# emc6907.net
KiCad netlist of a schematic drawn in EAGLE
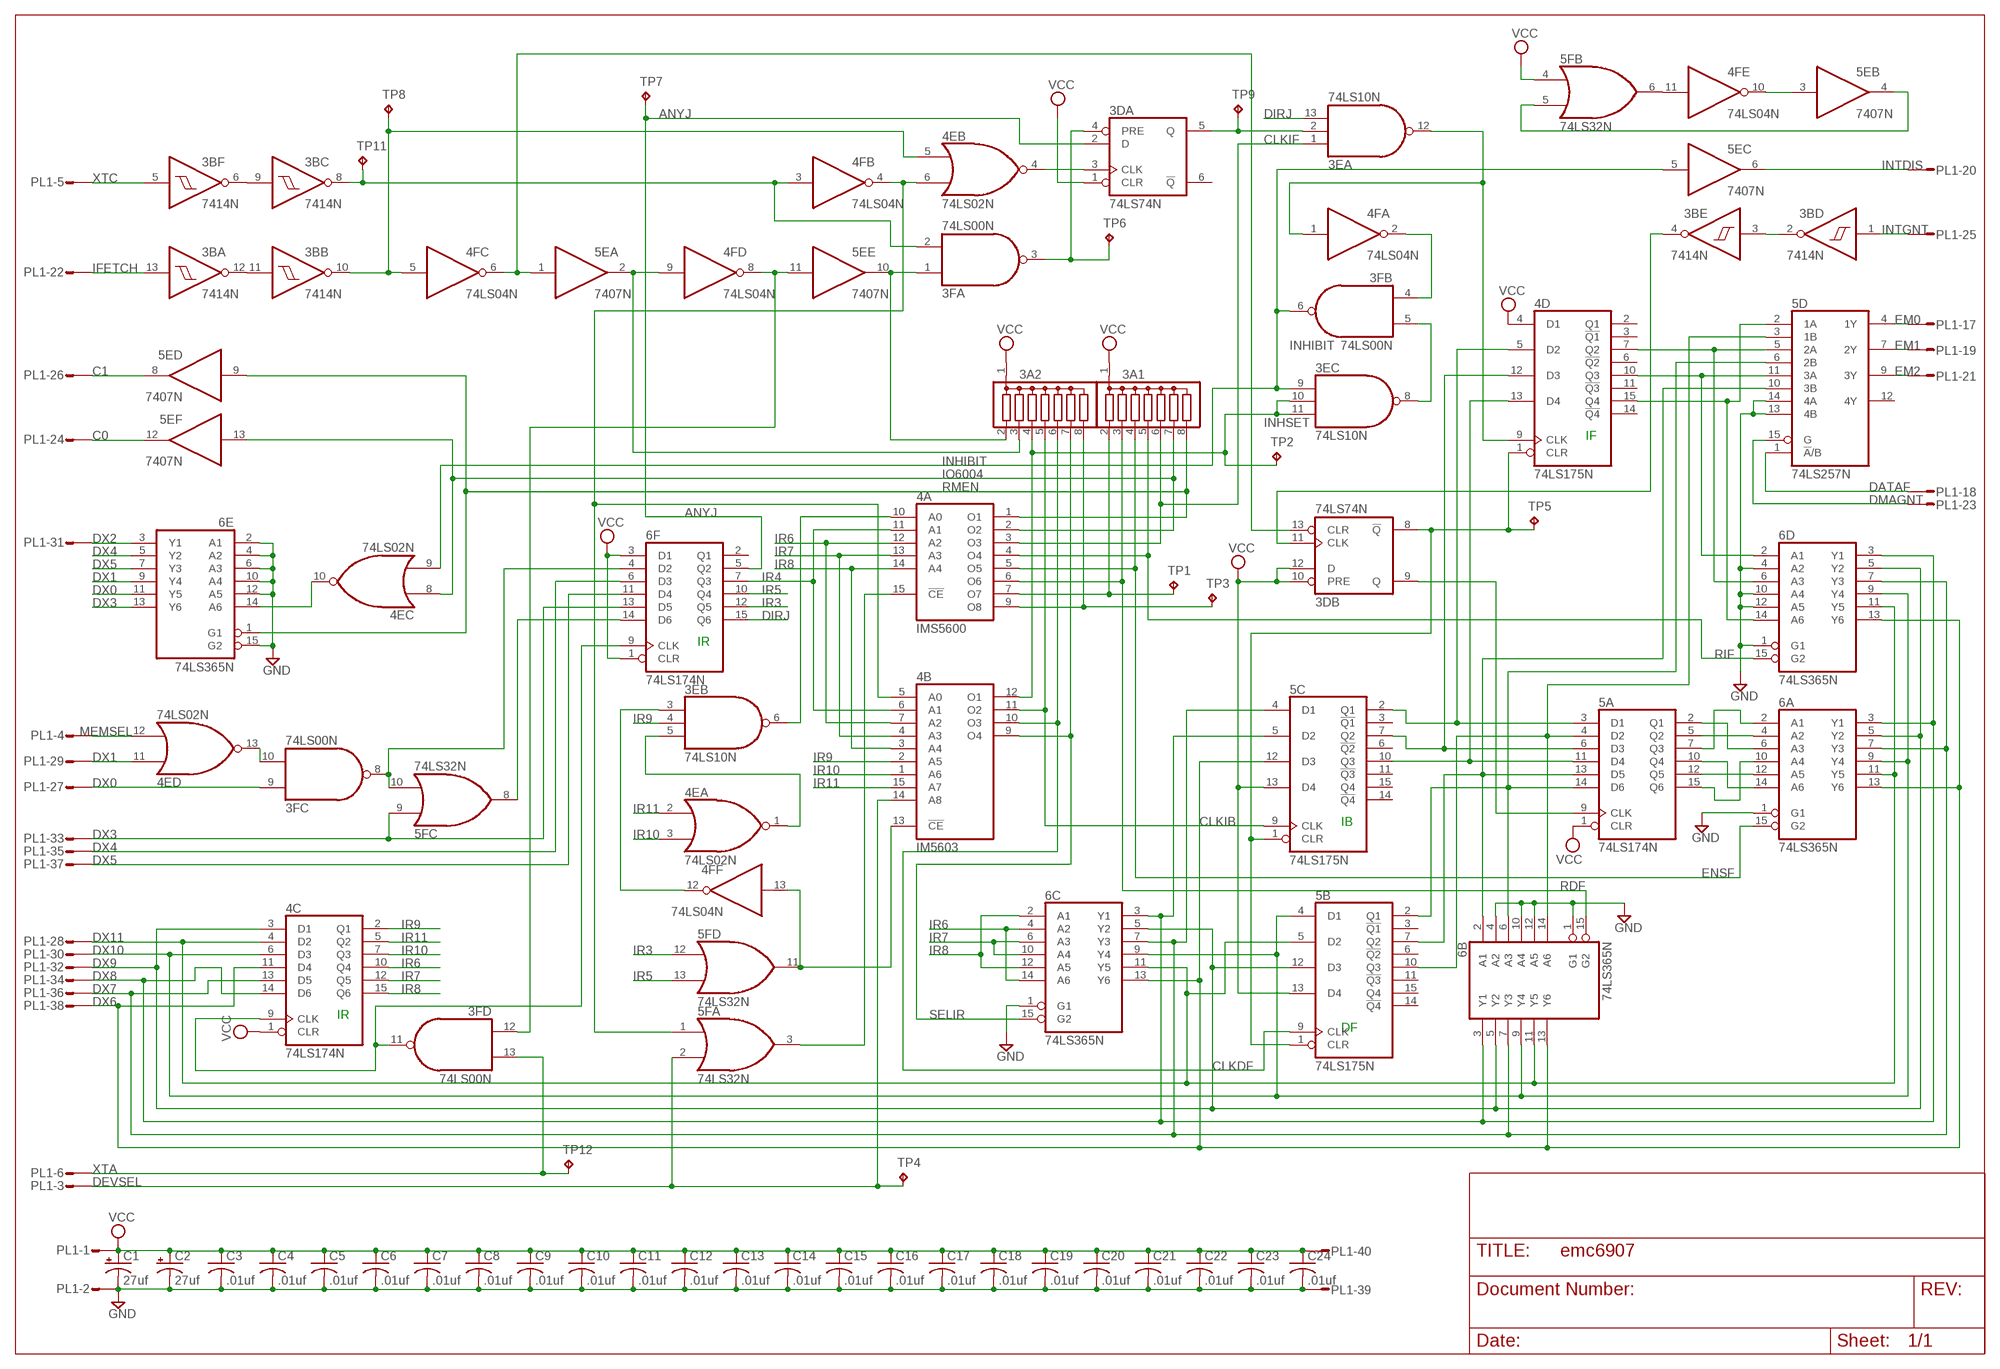
[diagram p0: schematic, sheet 1]

(export (version "E")
  (design (tool "Eeschema 10.0.6"))
  (components
    (comp (ref "3A1")
      (value "G07R")
      (footprint "eagle-import:SIL8")
      (libsource (lib "eagle-import") (part "G07R"))
    )
    (comp (ref "3A2")
      (value "G07R")
      (footprint "eagle-import:SIL8")
      (libsource (lib "eagle-import") (part "G07R"))
    )
    (comp (ref "3B")
      (value "7414N")
      (footprint "eagle-import:DIL14")
      (libsource (lib "eagle-import") (part "7414N"))
    )
    (comp (ref "3D")
      (value "74LS74N")
      (footprint "eagle-import:DIL14")
      (libsource (lib "eagle-import") (part "7474NLS"))
    )
    (comp (ref "3E")
      (value "74LS10N")
      (footprint "eagle-import:DIL14")
      (libsource (lib "eagle-import") (part "7410NLS"))
    )
    (comp (ref "3F")
      (value "74LS00N")
      (footprint "eagle-import:DIL14")
      (libsource (lib "eagle-import") (part "7400NLS"))
    )
    (comp (ref "4A")
      (value "IMS5600")
      (footprint "eagle-import:DIL16")
      (libsource (lib "eagle-import") (part "5600"))
    )
    (comp (ref "4B")
      (value "IM5603")
      (footprint "eagle-import:DIL16")
      (libsource (lib "eagle-import") (part "5306"))
    )
    (comp (ref "4C")
      (value "74LS174N")
      (footprint "eagle-import:DIL16")
      (libsource (lib "eagle-import") (part "74174NLS"))
    )
    (comp (ref "4D")
      (value "74LS175N")
      (footprint "eagle-import:DIL16")
      (libsource (lib "eagle-import") (part "74175NLS"))
    )
    (comp (ref "4E")
      (value "74LS02N")
      (footprint "eagle-import:DIL14")
      (libsource (lib "eagle-import") (part "7402NLS"))
    )
    (comp (ref "4F")
      (value "74LS04N")
      (footprint "eagle-import:DIL14")
      (libsource (lib "eagle-import") (part "7404NLS"))
    )
    (comp (ref "5A")
      (value "74LS174N")
      (footprint "eagle-import:DIL16")
      (libsource (lib "eagle-import") (part "74174NLS"))
    )
    (comp (ref "5B")
      (value "74LS175N")
      (footprint "eagle-import:DIL16")
      (libsource (lib "eagle-import") (part "74175NLS"))
    )
    (comp (ref "5C")
      (value "74LS175N")
      (footprint "eagle-import:DIL16")
      (libsource (lib "eagle-import") (part "74175NLS"))
    )
    (comp (ref "5D")
      (value "74LS257N")
      (footprint "eagle-import:DIL16")
      (libsource (lib "eagle-import") (part "74257NLS"))
    )
    (comp (ref "5E")
      (value "7407N")
      (footprint "eagle-import:DIL14")
      (libsource (lib "eagle-import") (part "7407N"))
    )
    (comp (ref "5F")
      (value "74LS32N")
      (footprint "eagle-import:DIL14")
      (libsource (lib "eagle-import") (part "7432NLS"))
    )
    (comp (ref "6A")
      (value "74LS365N")
      (footprint "eagle-import:DIL16")
      (libsource (lib "eagle-import") (part "74365NLS"))
    )
    (comp (ref "6B")
      (value "74LS365N")
      (footprint "eagle-import:DIL16")
      (libsource (lib "eagle-import") (part "74365NLS"))
    )
    (comp (ref "6C")
      (value "74LS365N")
      (footprint "eagle-import:DIL16")
      (libsource (lib "eagle-import") (part "74365NLS"))
    )
    (comp (ref "6D")
      (value "74LS365N")
      (footprint "eagle-import:DIL16")
      (libsource (lib "eagle-import") (part "74365NLS"))
    )
    (comp (ref "6E")
      (value "74LS365N")
      (footprint "eagle-import:DIL16")
      (libsource (lib "eagle-import") (part "74365NLS"))
    )
    (comp (ref "6F")
      (value "74LS174N")
      (footprint "eagle-import:DIL16")
      (libsource (lib "eagle-import") (part "74174NLS"))
    )
    (comp (ref "C1")
      (value "27uf")
      (footprint "eagle-import:E22-6")
      (libsource (lib "eagle-import") (part "CPOL-USE22-6AXIAL"))
    )
    (comp (ref "C2")
      (value "27uf")
      (footprint "eagle-import:E22-6")
      (libsource (lib "eagle-import") (part "CPOL-USE22-6AXIAL"))
    )
    (comp (ref "C3")
      (value ".01uf")
      (footprint "eagle-import:C050-025X075")
      (libsource (lib "eagle-import") (part "C-US050-025X075"))
    )
    (comp (ref "C4")
      (value ".01uf")
      (footprint "eagle-import:C050-025X075")
      (libsource (lib "eagle-import") (part "C-US050-025X075"))
    )
    (comp (ref "C5")
      (value ".01uf")
      (footprint "eagle-import:C050-025X075")
      (libsource (lib "eagle-import") (part "C-US050-025X075"))
    )
    (comp (ref "C6")
      (value ".01uf")
      (footprint "eagle-import:C050-025X075")
      (libsource (lib "eagle-import") (part "C-US050-025X075"))
    )
    (comp (ref "C7")
      (value ".01uf")
      (footprint "eagle-import:C050-025X075")
      (libsource (lib "eagle-import") (part "C-US050-025X075"))
    )
    (comp (ref "C8")
      (value ".01uf")
      (footprint "eagle-import:C050-025X075")
      (libsource (lib "eagle-import") (part "C-US050-025X075"))
    )
    (comp (ref "C9")
      (value ".01uf")
      (footprint "eagle-import:C050-025X075")
      (libsource (lib "eagle-import") (part "C-US050-025X075"))
    )
    (comp (ref "C10")
      (value ".01uf")
      (footprint "eagle-import:C050-025X075")
      (libsource (lib "eagle-import") (part "C-US050-025X075"))
    )
    (comp (ref "C11")
      (value ".01uf")
      (footprint "eagle-import:C050-025X075")
      (libsource (lib "eagle-import") (part "C-US050-025X075"))
    )
    (comp (ref "C12")
      (value ".01uf")
      (footprint "eagle-import:C050-025X075")
      (libsource (lib "eagle-import") (part "C-US050-025X075"))
    )
    (comp (ref "C13")
      (value ".01uf")
      (footprint "eagle-import:C050-025X075")
      (libsource (lib "eagle-import") (part "C-US050-025X075"))
    )
    (comp (ref "C14")
      (value ".01uf")
      (footprint "eagle-import:C050-025X075")
      (libsource (lib "eagle-import") (part "C-US050-025X075"))
    )
    (comp (ref "C15")
      (value ".01uf")
      (footprint "eagle-import:C050-025X075")
      (libsource (lib "eagle-import") (part "C-US050-025X075"))
    )
    (comp (ref "C16")
      (value ".01uf")
      (footprint "eagle-import:C050-025X075")
      (libsource (lib "eagle-import") (part "C-US050-025X075"))
    )
    (comp (ref "C17")
      (value ".01uf")
      (footprint "eagle-import:C050-025X075")
      (libsource (lib "eagle-import") (part "C-US050-025X075"))
    )
    (comp (ref "C18")
      (value ".01uf")
      (footprint "eagle-import:C050-025X075")
      (libsource (lib "eagle-import") (part "C-US050-025X075"))
    )
    (comp (ref "C19")
      (value ".01uf")
      (footprint "eagle-import:C050-025X075")
      (libsource (lib "eagle-import") (part "C-US050-025X075"))
    )
    (comp (ref "C20")
      (value ".01uf")
      (footprint "eagle-import:C050-025X075")
      (libsource (lib "eagle-import") (part "C-US050-025X075"))
    )
    (comp (ref "C21")
      (value ".01uf")
      (footprint "eagle-import:C050-025X075")
      (libsource (lib "eagle-import") (part "C-US050-025X075"))
    )
    (comp (ref "C22")
      (value ".01uf")
      (footprint "eagle-import:C050-025X075")
      (libsource (lib "eagle-import") (part "C-US050-025X075"))
    )
    (comp (ref "C23")
      (value ".01uf")
      (footprint "eagle-import:C050-025X075")
      (libsource (lib "eagle-import") (part "C-US050-025X075"))
    )
    (comp (ref "C24")
      (value ".01uf")
      (footprint "eagle-import:C050-025X075")
      (libsource (lib "eagle-import") (part "C-US050-025X075"))
    )
    (comp (ref "PL1")
      (value "40VS")
      (footprint "eagle-import:40V")
      (libsource (lib "eagle-import") (part "40VS"))
    )
    (comp (ref "TP1")
      (value "TPPAD1-13")
      (footprint "eagle-import:P1-13")
      (libsource (lib "eagle-import") (part "TPPAD1-13"))
    )
    (comp (ref "TP2")
      (value "TPPAD1-13")
      (footprint "eagle-import:P1-13")
      (libsource (lib "eagle-import") (part "TPPAD1-13"))
    )
    (comp (ref "TP3")
      (value "TPPAD1-13")
      (footprint "eagle-import:P1-13")
      (libsource (lib "eagle-import") (part "TPPAD1-13"))
    )
    (comp (ref "TP4")
      (value "TPPAD1-13")
      (footprint "eagle-import:P1-13")
      (libsource (lib "eagle-import") (part "TPPAD1-13"))
    )
    (comp (ref "TP5")
      (value "TPPAD1-13")
      (footprint "eagle-import:P1-13")
      (libsource (lib "eagle-import") (part "TPPAD1-13"))
    )
    (comp (ref "TP6")
      (value "TPPAD1-13")
      (footprint "eagle-import:P1-13")
      (libsource (lib "eagle-import") (part "TPPAD1-13"))
    )
    (comp (ref "TP7")
      (value "TPPAD1-13")
      (footprint "eagle-import:P1-13")
      (libsource (lib "eagle-import") (part "TPPAD1-13"))
    )
    (comp (ref "TP8")
      (value "TPPAD1-13")
      (footprint "eagle-import:P1-13")
      (libsource (lib "eagle-import") (part "TPPAD1-13"))
    )
    (comp (ref "TP9")
      (value "TPPAD1-13")
      (footprint "eagle-import:P1-13")
      (libsource (lib "eagle-import") (part "TPPAD1-13"))
    )
    (comp (ref "TP11")
      (value "TPPAD1-13")
      (footprint "eagle-import:P1-13")
      (libsource (lib "eagle-import") (part "TPPAD1-13"))
    )
    (comp (ref "TP12")
      (value "TPPAD1-13")
      (footprint "eagle-import:P1-13")
      (libsource (lib "eagle-import") (part "TPPAD1-13"))
    )
  )
  (nets
    (net (code "1") (name "/ANYJ") (class "Default")
      (node (ref "3D") (pin "2") (pinfunction "D_2") (pintype "input"))
      (node (ref "6F") (pin "5") (pinfunction "Q2_5") (pintype "output"))
      (node (ref "TP7") (pin "TP") (pinfunction "TP_TP") (pintype "input"))
    )
    (net (code "2") (name "/C0") (class "Default")
      (node (ref "5E") (pin "12") (pinfunction "O_12") (pintype "open_collector"))
      (node (ref "PL1") (pin "24") (pinfunction "S_24") (pintype "passive"))
    )
    (net (code "3") (name "/C1") (class "Default")
      (node (ref "5E") (pin "8") (pinfunction "O_8") (pintype "open_collector"))
      (node (ref "PL1") (pin "26") (pinfunction "S_26") (pintype "passive"))
    )
    (net (code "4") (name "/CLKDF") (class "Default")
      (node (ref "3A2") (pin "6") (pinfunction "6_6") (pintype "passive"))
      (node (ref "4B") (pin "10") (pinfunction "O3_10") (pintype "tri_state"))
      (node (ref "5B") (pin "9") (pinfunction "CLK_9") (pintype "input"))
    )
    (net (code "5") (name "/CLKIB") (class "Default")
      (node (ref "3A2") (pin "5") (pinfunction "5_5") (pintype "passive"))
      (node (ref "4B") (pin "11") (pinfunction "O2_11") (pintype "tri_state"))
      (node (ref "5C") (pin "9") (pinfunction "CLK_9") (pintype "input"))
    )
    (net (code "6") (name "/CLKIF") (class "Default")
      (node (ref "3A1") (pin "6") (pinfunction "6_6") (pintype "passive"))
      (node (ref "3E") (pin "1") (pinfunction "I0_1") (pintype "input"))
      (node (ref "4A") (pin "3") (pinfunction "O3_3") (pintype "open_collector"))
    )
    (net (code "7") (name "/DATAF") (class "Default")
      (node (ref "5D") (pin "1") (pinfunction "~{A}/B_1") (pintype "input"))
      (node (ref "PL1") (pin "18") (pinfunction "S_18") (pintype "passive"))
    )
    (net (code "8") (name "/DEVSEL") (class "Default")
      (node (ref "4B") (pin "14") (pinfunction "A8_14") (pintype "input"))
      (node (ref "5F") (pin "2") (pinfunction "I1_2") (pintype "input"))
      (node (ref "PL1") (pin "3") (pinfunction "S_3") (pintype "passive"))
      (node (ref "TP4") (pin "TP") (pinfunction "TP_TP") (pintype "input"))
    )
    (net (code "9") (name "/DIRJ") (class "Default")
      (node (ref "3E") (pin "13") (pinfunction "I2_13") (pintype "input"))
      (node (ref "6F") (pin "15") (pinfunction "Q6_15") (pintype "output"))
    )
    (net (code "10") (name "/DMAGNT") (class "Default")
      (node (ref "5D") (pin "15") (pinfunction "G_15") (pintype "input"))
      (node (ref "PL1") (pin "23") (pinfunction "S_23") (pintype "passive"))
    )
    (net (code "11") (name "/DX0") (class "Default")
      (node (ref "3F") (pin "9") (pinfunction "I0_9") (pintype "input"))
      (node (ref "6E") (pin "11") (pinfunction "Y5_11") (pintype "tri_state"))
      (node (ref "PL1") (pin "27") (pinfunction "S_27") (pintype "passive"))
    )
    (net (code "12") (name "/DX1") (class "Default")
      (node (ref "4E") (pin "11") (pinfunction "I0_11") (pintype "input"))
      (node (ref "6E") (pin "9") (pinfunction "Y4_9") (pintype "tri_state"))
      (node (ref "PL1") (pin "29") (pinfunction "S_29") (pintype "passive"))
    )
    (net (code "13") (name "/DX2") (class "Default")
      (node (ref "6E") (pin "3") (pinfunction "Y1_3") (pintype "tri_state"))
      (node (ref "PL1") (pin "31") (pinfunction "S_31") (pintype "passive"))
    )
    (net (code "14") (name "/DX3") (class "Default")
      (node (ref "5F") (pin "9") (pinfunction "I0_9") (pintype "input"))
      (node (ref "6E") (pin "13") (pinfunction "Y6_13") (pintype "tri_state"))
      (node (ref "6F") (pin "13") (pinfunction "D5_13") (pintype "input"))
      (node (ref "PL1") (pin "33") (pinfunction "S_33") (pintype "passive"))
    )
    (net (code "15") (name "/DX4") (class "Default")
      (node (ref "6E") (pin "5") (pinfunction "Y2_5") (pintype "tri_state"))
      (node (ref "6F") (pin "6") (pinfunction "D3_6") (pintype "input"))
      (node (ref "PL1") (pin "35") (pinfunction "S_35") (pintype "passive"))
    )
    (net (code "16") (name "/DX5") (class "Default")
      (node (ref "6E") (pin "7") (pinfunction "Y3_7") (pintype "tri_state"))
      (node (ref "6F") (pin "11") (pinfunction "D4_11") (pintype "input"))
      (node (ref "PL1") (pin "37") (pinfunction "S_37") (pintype "passive"))
    )
    (net (code "17") (name "/DX6") (class "Default")
      (node (ref "4C") (pin "11") (pinfunction "D4_11") (pintype "input"))
      (node (ref "5C") (pin "12") (pinfunction "D3_12") (pintype "input"))
      (node (ref "6A") (pin "13") (pinfunction "Y6_13") (pintype "tri_state"))
      (node (ref "6B") (pin "13") (pinfunction "Y6_13") (pintype "tri_state"))
      (node (ref "6C") (pin "13") (pinfunction "Y6_13") (pintype "tri_state"))
      (node (ref "6D") (pin "13") (pinfunction "Y6_13") (pintype "tri_state"))
      (node (ref "PL1") (pin "38") (pinfunction "S_38") (pintype "passive"))
    )
    (net (code "18") (name "/DX7") (class "Default")
      (node (ref "4C") (pin "13") (pinfunction "D5_13") (pintype "input"))
      (node (ref "5C") (pin "4") (pinfunction "D1_4") (pintype "input"))
      (node (ref "6A") (pin "7") (pinfunction "Y3_7") (pintype "tri_state"))
      (node (ref "6B") (pin "7") (pinfunction "Y3_7") (pintype "tri_state"))
      (node (ref "6C") (pin "7") (pinfunction "Y3_7") (pintype "tri_state"))
      (node (ref "6D") (pin "7") (pinfunction "Y3_7") (pintype "tri_state"))
      (node (ref "PL1") (pin "36") (pinfunction "S_36") (pintype "passive"))
    )
    (net (code "19") (name "/DX8") (class "Default")
      (node (ref "4C") (pin "14") (pinfunction "D6_14") (pintype "input"))
      (node (ref "5C") (pin "5") (pinfunction "D2_5") (pintype "input"))
      (node (ref "6A") (pin "3") (pinfunction "Y1_3") (pintype "tri_state"))
      (node (ref "6B") (pin "3") (pinfunction "Y1_3") (pintype "tri_state"))
      (node (ref "6C") (pin "3") (pinfunction "Y1_3") (pintype "tri_state"))
      (node (ref "6D") (pin "3") (pinfunction "Y1_3") (pintype "tri_state"))
      (node (ref "PL1") (pin "34") (pinfunction "S_34") (pintype "passive"))
    )
    (net (code "20") (name "/DX9") (class "Default")
      (node (ref "4C") (pin "3") (pinfunction "D1_3") (pintype "input"))
      (node (ref "5B") (pin "12") (pinfunction "D3_12") (pintype "input"))
      (node (ref "6A") (pin "5") (pinfunction "Y2_5") (pintype "tri_state"))
      (node (ref "6B") (pin "5") (pinfunction "Y2_5") (pintype "tri_state"))
      (node (ref "6C") (pin "5") (pinfunction "Y2_5") (pintype "tri_state"))
      (node (ref "6D") (pin "5") (pinfunction "Y2_5") (pintype "tri_state"))
      (node (ref "PL1") (pin "32") (pinfunction "S_32") (pintype "passive"))
    )
    (net (code "21") (name "/DX10") (class "Default")
      (node (ref "4C") (pin "6") (pinfunction "D3_6") (pintype "input"))
      (node (ref "5B") (pin "4") (pinfunction "D1_4") (pintype "input"))
      (node (ref "6A") (pin "9") (pinfunction "Y4_9") (pintype "tri_state"))
      (node (ref "6B") (pin "9") (pinfunction "Y4_9") (pintype "tri_state"))
      (node (ref "6C") (pin "9") (pinfunction "Y4_9") (pintype "tri_state"))
      (node (ref "6D") (pin "9") (pinfunction "Y4_9") (pintype "tri_state"))
      (node (ref "PL1") (pin "30") (pinfunction "S_30") (pintype "passive"))
    )
    (net (code "22") (name "/DX11") (class "Default")
      (node (ref "4C") (pin "4") (pinfunction "D2_4") (pintype "input"))
      (node (ref "5B") (pin "5") (pinfunction "D2_5") (pintype "input"))
      (node (ref "6A") (pin "11") (pinfunction "Y5_11") (pintype "tri_state"))
      (node (ref "6B") (pin "11") (pinfunction "Y5_11") (pintype "tri_state"))
      (node (ref "6C") (pin "11") (pinfunction "Y5_11") (pintype "tri_state"))
      (node (ref "6D") (pin "11") (pinfunction "Y5_11") (pintype "tri_state"))
      (node (ref "PL1") (pin "28") (pinfunction "S_28") (pintype "passive"))
    )
    (net (code "23") (name "/EM0") (class "Default")
      (node (ref "5D") (pin "4") (pinfunction "1Y_4") (pintype "tri_state"))
      (node (ref "PL1") (pin "17") (pinfunction "S_17") (pintype "passive"))
    )
    (net (code "24") (name "/EM1") (class "Default")
      (node (ref "5D") (pin "7") (pinfunction "2Y_7") (pintype "tri_state"))
      (node (ref "PL1") (pin "19") (pinfunction "S_19") (pintype "passive"))
    )
    (net (code "25") (name "/EM2") (class "Default")
      (node (ref "5D") (pin "9") (pinfunction "3Y_9") (pintype "tri_state"))
      (node (ref "PL1") (pin "21") (pinfunction "S_21") (pintype "passive"))
    )
    (net (code "26") (name "/ENSF") (class "Default")
      (node (ref "3A1") (pin "4") (pinfunction "4_4") (pintype "passive"))
      (node (ref "4A") (pin "5") (pinfunction "O5_5") (pintype "open_collector"))
      (node (ref "6A") (pin "15") (pinfunction "G2_15") (pintype "input"))
    )
    (net (code "27") (name "/IFETCH") (class "Default")
      (node (ref "3B") (pin "13") (pinfunction "I_13") (pintype "input"))
      (node (ref "PL1") (pin "22") (pinfunction "S_22") (pintype "passive"))
    )
    (net (code "28") (name "/INHIBIT") (class "Default")
      (node (ref "3E") (pin "9") (pinfunction "I0_9") (pintype "input"))
      (node (ref "3F") (pin "6") (pinfunction "O_6") (pintype "output"))
      (node (ref "4E") (pin "9") (pinfunction "I1_9") (pintype "input"))
      (node (ref "5E") (pin "5") (pinfunction "I_5") (pintype "input"))
    )
    (net (code "29") (name "/INHSET") (class "Default")
      (node (ref "3A2") (pin "4") (pinfunction "4_4") (pintype "passive"))
      (node (ref "3E") (pin "10") (pinfunction "I1_10") (pintype "input"))
      (node (ref "3E") (pin "11") (pinfunction "I2_11") (pintype "input"))
      (node (ref "4B") (pin "12") (pinfunction "O1_12") (pintype "tri_state"))
      (node (ref "TP2") (pin "TP") (pinfunction "TP_TP") (pintype "input"))
    )
    (net (code "30") (name "/INTDIS") (class "Default")
      (node (ref "5E") (pin "6") (pinfunction "O_6") (pintype "open_collector"))
      (node (ref "PL1") (pin "20") (pinfunction "S_20") (pintype "passive"))
    )
    (net (code "31") (name "/INTGNT") (class "Default")
      (node (ref "3B") (pin "1") (pinfunction "I_1") (pintype "input"))
      (node (ref "PL1") (pin "25") (pinfunction "S_25") (pintype "passive"))
    )
    (net (code "32") (name "/IO6004") (class "Default")
      (node (ref "3A1") (pin "7") (pinfunction "7_7") (pintype "passive"))
      (node (ref "4A") (pin "2") (pinfunction "O2_2") (pintype "open_collector"))
      (node (ref "4E") (pin "8") (pinfunction "I0_8") (pintype "input"))
      (node (ref "5E") (pin "13") (pinfunction "I_13") (pintype "input"))
    )
    (net (code "33") (name "/IR3") (class "Default")
      (node (ref "5F") (pin "12") (pinfunction "I0_12") (pintype "input"))
      (node (ref "6F") (pin "12") (pinfunction "Q5_12") (pintype "output"))
    )
    (net (code "34") (name "/IR4") (class "Default")
      (node (ref "4A") (pin "11") (pinfunction "A1_11") (pintype "input"))
      (node (ref "4B") (pin "6") (pinfunction "A1_6") (pintype "input"))
      (node (ref "6F") (pin "7") (pinfunction "Q3_7") (pintype "output"))
    )
    (net (code "35") (name "/IR5") (class "Default")
      (node (ref "5F") (pin "13") (pinfunction "I1_13") (pintype "input"))
      (node (ref "6F") (pin "10") (pinfunction "Q4_10") (pintype "output"))
    )
    (net (code "36") (name "/IR6") (class "Default")
      (node (ref "4A") (pin "12") (pinfunction "A2_12") (pintype "input"))
      (node (ref "4B") (pin "7") (pinfunction "A2_7") (pintype "input"))
      (node (ref "4C") (pin "10") (pinfunction "Q4_10") (pintype "output"))
      (node (ref "6C") (pin "14") (pinfunction "A6_14") (pintype "input"))
      (node (ref "6C") (pin "4") (pinfunction "A2_4") (pintype "input"))
    )
    (net (code "37") (name "/IR7") (class "Default")
      (node (ref "4A") (pin "13") (pinfunction "A3_13") (pintype "input"))
      (node (ref "4B") (pin "4") (pinfunction "A3_4") (pintype "input"))
      (node (ref "4C") (pin "12") (pinfunction "Q5_12") (pintype "output"))
      (node (ref "6C") (pin "10") (pinfunction "A4_10") (pintype "input"))
      (node (ref "6C") (pin "6") (pinfunction "A3_6") (pintype "input"))
    )
    (net (code "38") (name "/IR8") (class "Default")
      (node (ref "4A") (pin "14") (pinfunction "A4_14") (pintype "input"))
      (node (ref "4B") (pin "3") (pinfunction "A4_3") (pintype "input"))
      (node (ref "4C") (pin "15") (pinfunction "Q6_15") (pintype "output"))
      (node (ref "6C") (pin "12") (pinfunction "A5_12") (pintype "input"))
      (node (ref "6C") (pin "2") (pinfunction "A1_2") (pintype "input"))
    )
    (net (code "39") (name "/IR9") (class "Default")
      (node (ref "3E") (pin "4") (pinfunction "I1_4") (pintype "input"))
      (node (ref "4B") (pin "2") (pinfunction "A5_2") (pintype "input"))
      (node (ref "4C") (pin "2") (pinfunction "Q1_2") (pintype "output"))
    )
    (net (code "40") (name "/IR10") (class "Default")
      (node (ref "4B") (pin "1") (pinfunction "A6_1") (pintype "input"))
      (node (ref "4C") (pin "7") (pinfunction "Q3_7") (pintype "output"))
      (node (ref "4E") (pin "3") (pinfunction "I1_3") (pintype "input"))
    )
    (net (code "41") (name "/IR11") (class "Default")
      (node (ref "4B") (pin "15") (pinfunction "A7_15") (pintype "input"))
      (node (ref "4C") (pin "5") (pinfunction "Q2_5") (pintype "output"))
      (node (ref "4E") (pin "2") (pinfunction "I0_2") (pintype "input"))
    )
    (net (code "42") (name "/MEMSEL") (class "Default")
      (node (ref "4E") (pin "12") (pinfunction "I1_12") (pintype "input"))
      (node (ref "PL1") (pin "4") (pinfunction "S_4") (pintype "passive"))
    )
    (net (code "43") (name "/RDF") (class "Default")
      (node (ref "3A1") (pin "3") (pinfunction "3_3") (pintype "passive"))
      (node (ref "4A") (pin "6") (pinfunction "O6_6") (pintype "open_collector"))
      (node (ref "6B") (pin "15") (pinfunction "G2_15") (pintype "input"))
    )
    (net (code "44") (name "/RIF") (class "Default")
      (node (ref "3A1") (pin "5") (pinfunction "5_5") (pintype "passive"))
      (node (ref "4A") (pin "4") (pinfunction "O4_4") (pintype "open_collector"))
      (node (ref "6D") (pin "15") (pinfunction "G2_15") (pintype "input"))
    )
    (net (code "45") (name "/RMEN") (class "Default")
      (node (ref "3A1") (pin "8") (pinfunction "8_8") (pintype "passive"))
      (node (ref "4A") (pin "1") (pinfunction "O1_1") (pintype "open_collector"))
      (node (ref "5E") (pin "9") (pinfunction "I_9") (pintype "input"))
      (node (ref "6E") (pin "1") (pinfunction "G1_1") (pintype "input"))
    )
    (net (code "46") (name "/SELIR") (class "Default")
      (node (ref "3A2") (pin "7") (pinfunction "7_7") (pintype "passive"))
      (node (ref "4B") (pin "9") (pinfunction "O4_9") (pintype "tri_state"))
      (node (ref "6C") (pin "15") (pinfunction "G2_15") (pintype "input"))
    )
    (net (code "47") (name "/XTA") (class "Default")
      (node (ref "3F") (pin "13") (pinfunction "I1_13") (pintype "input"))
      (node (ref "PL1") (pin "6") (pinfunction "S_6") (pintype "passive"))
      (node (ref "TP12") (pin "TP") (pinfunction "TP_TP") (pintype "input"))
    )
    (net (code "48") (name "/XTC") (class "Default")
      (node (ref "3B") (pin "5") (pinfunction "I_5") (pintype "input"))
      (node (ref "PL1") (pin "5") (pinfunction "S_5") (pintype "passive"))
    )
    (net (code "49") (name "GND") (class "Default")
      (node (ref "5D") (pin "13") (pinfunction "4B_13") (pintype "input"))
      (node (ref "5D") (pin "14") (pinfunction "4A_14") (pintype "input"))
      (node (ref "6A") (pin "1") (pinfunction "G1_1") (pintype "input"))
      (node (ref "6B") (pin "1") (pinfunction "G1_1") (pintype "input"))
      (node (ref "6B") (pin "10") (pinfunction "A4_10") (pintype "input"))
      (node (ref "6B") (pin "12") (pinfunction "A5_12") (pintype "input"))
      (node (ref "6B") (pin "4") (pinfunction "A2_4") (pintype "input"))
      (node (ref "6C") (pin "1") (pinfunction "G1_1") (pintype "input"))
      (node (ref "6D") (pin "1") (pinfunction "G1_1") (pintype "input"))
      (node (ref "6D") (pin "10") (pinfunction "A4_10") (pintype "input"))
      (node (ref "6D") (pin "12") (pinfunction "A5_12") (pintype "input"))
      (node (ref "6D") (pin "4") (pinfunction "A2_4") (pintype "input"))
      (node (ref "6E") (pin "10") (pinfunction "A4_10") (pintype "input"))
      (node (ref "6E") (pin "12") (pinfunction "A5_12") (pintype "input"))
      (node (ref "6E") (pin "15") (pinfunction "G2_15") (pintype "input"))
      (node (ref "6E") (pin "2") (pinfunction "A1_2") (pintype "input"))
      (node (ref "6E") (pin "4") (pinfunction "A2_4") (pintype "input"))
      (node (ref "6E") (pin "6") (pinfunction "A3_6") (pintype "input"))
      (node (ref "C1") (pin "-") (pinfunction "-_-") (pintype "passive"))
      (node (ref "C10") (pin "2") (pinfunction "2_2") (pintype "passive"))
      (node (ref "C11") (pin "2") (pinfunction "2_2") (pintype "passive"))
      (node (ref "C12") (pin "2") (pinfunction "2_2") (pintype "passive"))
      (node (ref "C13") (pin "2") (pinfunction "2_2") (pintype "passive"))
      (node (ref "C14") (pin "2") (pinfunction "2_2") (pintype "passive"))
      (node (ref "C15") (pin "2") (pinfunction "2_2") (pintype "passive"))
      (node (ref "C16") (pin "2") (pinfunction "2_2") (pintype "passive"))
      (node (ref "C17") (pin "2") (pinfunction "2_2") (pintype "passive"))
      (node (ref "C18") (pin "2") (pinfunction "2_2") (pintype "passive"))
      (node (ref "C19") (pin "2") (pinfunction "2_2") (pintype "passive"))
      (node (ref "C2") (pin "-") (pinfunction "-_-") (pintype "passive"))
      (node (ref "C20") (pin "2") (pinfunction "2_2") (pintype "passive"))
      (node (ref "C21") (pin "2") (pinfunction "2_2") (pintype "passive"))
      (node (ref "C22") (pin "2") (pinfunction "2_2") (pintype "passive"))
      (node (ref "C23") (pin "2") (pinfunction "2_2") (pintype "passive"))
      (node (ref "C24") (pin "2") (pinfunction "2_2") (pintype "passive"))
      (node (ref "C3") (pin "2") (pinfunction "2_2") (pintype "passive"))
      (node (ref "C4") (pin "2") (pinfunction "2_2") (pintype "passive"))
      (node (ref "C5") (pin "2") (pinfunction "2_2") (pintype "passive"))
      (node (ref "C6") (pin "2") (pinfunction "2_2") (pintype "passive"))
      (node (ref "C7") (pin "2") (pinfunction "2_2") (pintype "passive"))
      (node (ref "C8") (pin "2") (pinfunction "2_2") (pintype "passive"))
      (node (ref "C9") (pin "2") (pinfunction "2_2") (pintype "passive"))
      (node (ref "PL1") (pin "2") (pinfunction "S_2") (pintype "passive"))
      (node (ref "PL1") (pin "39") (pinfunction "S_39") (pintype "passive"))
    )
    (net (code "50") (name "Net-(3BA-O)") (class "Default")
      (node (ref "3B") (pin "11") (pinfunction "I_11") (pintype "input"))
      (node (ref "3B") (pin "12") (pinfunction "O_12") (pintype "output"))
    )
    (net (code "51") (name "Net-(3BB-O)") (class "Default")
      (node (ref "3B") (pin "10") (pinfunction "O_10") (pintype "output"))
      (node (ref "4E") (pin "5") (pinfunction "I0_5") (pintype "input"))
      (node (ref "4F") (pin "5") (pinfunction "I_5") (pintype "input"))
      (node (ref "TP8") (pin "TP") (pinfunction "TP_TP") (pintype "input"))
    )
    (net (code "52") (name "Net-(3BC-I)") (class "Default")
      (node (ref "3B") (pin "6") (pinfunction "O_6") (pintype "output"))
      (node (ref "3B") (pin "9") (pinfunction "I_9") (pintype "input"))
    )
    (net (code "53") (name "Net-(3BC-O)") (class "Default")
      (node (ref "3B") (pin "8") (pinfunction "O_8") (pintype "output"))
      (node (ref "3F") (pin "2") (pinfunction "I1_2") (pintype "input"))
      (node (ref "4F") (pin "3") (pinfunction "I_3") (pintype "input"))
      (node (ref "TP11") (pin "TP") (pinfunction "TP_TP") (pintype "input"))
    )
    (net (code "54") (name "Net-(3BD-O)") (class "Default")
      (node (ref "3B") (pin "2") (pinfunction "O_2") (pintype "output"))
      (node (ref "3B") (pin "3") (pinfunction "I_3") (pintype "input"))
    )
    (net (code "55") (name "Net-(3BE-O)") (class "Default")
      (node (ref "3B") (pin "4") (pinfunction "O_4") (pintype "output"))
      (node (ref "3D") (pin "11") (pinfunction "CLK_11") (pintype "input"))
    )
    (net (code "56") (name "Net-(3DA-CLK)") (class "Default")
      (node (ref "3D") (pin "3") (pinfunction "CLK_3") (pintype "input"))
      (node (ref "4E") (pin "4") (pinfunction "O_4") (pintype "output"))
    )
    (net (code "57") (name "Net-(3DA-PRE)") (class "Default")
      (node (ref "3D") (pin "4") (pinfunction "PRE_4") (pintype "input"))
      (node (ref "3F") (pin "3") (pinfunction "O_3") (pintype "output"))
      (node (ref "TP6") (pin "TP") (pinfunction "TP_TP") (pintype "input"))
    )
    (net (code "58") (name "Net-(3DA-Q)") (class "Default")
      (node (ref "3D") (pin "5") (pinfunction "Q_5") (pintype "output"))
      (node (ref "3E") (pin "2") (pinfunction "I1_2") (pintype "input"))
      (node (ref "TP9") (pin "TP") (pinfunction "TP_TP") (pintype "input"))
    )
    (net (code "59") (name "Net-(3DB-CLR)") (class "Default")
      (node (ref "3D") (pin "13") (pinfunction "CLR_13") (pintype "input"))
      (node (ref "4F") (pin "6") (pinfunction "O_6") (pintype "output"))
      (node (ref "5E") (pin "1") (pinfunction "I_1") (pintype "input"))
    )
    (net (code "60") (name "Net-(3DB-Q)") (class "Default")
      (node (ref "3D") (pin "9") (pinfunction "Q_9") (pintype "output"))
      (node (ref "5A") (pin "9") (pinfunction "CLK_9") (pintype "input"))
    )
    (net (code "61") (name "Net-(3DB-~{Q})") (class "Default")
      (node (ref "3D") (pin "8") (pinfunction "~{Q}_8") (pintype "output"))
      (node (ref "4D") (pin "1") (pinfunction "CLR_1") (pintype "input"))
      (node (ref "5B") (pin "1") (pinfunction "CLR_1") (pintype "input"))
      (node (ref "5C") (pin "1") (pinfunction "CLR_1") (pintype "input"))
      (node (ref "TP5") (pin "TP") (pinfunction "TP_TP") (pintype "input"))
    )
    (net (code "62") (name "Net-(3EA-O)") (class "Default")
      (node (ref "3E") (pin "12") (pinfunction "O_12") (pintype "output"))
      (node (ref "4D") (pin "9") (pinfunction "CLK_9") (pintype "input"))
      (node (ref "4F") (pin "1") (pinfunction "I_1") (pintype "input"))
    )
    (net (code "63") (name "Net-(3EB-I0)") (class "Default")
      (node (ref "3E") (pin "3") (pinfunction "I0_3") (pintype "input"))
      (node (ref "4F") (pin "12") (pinfunction "O_12") (pintype "output"))
    )
    (net (code "64") (name "Net-(3EB-I2)") (class "Default")
      (node (ref "3E") (pin "5") (pinfunction "I2_5") (pintype "input"))
      (node (ref "4E") (pin "1") (pinfunction "O_1") (pintype "output"))
    )
    (net (code "65") (name "Net-(3EB-O)") (class "Default")
      (node (ref "3E") (pin "6") (pinfunction "O_6") (pintype "output"))
      (node (ref "4A") (pin "10") (pinfunction "A0_10") (pintype "input"))
    )
    (net (code "66") (name "Net-(3EC-O)") (class "Default")
      (node (ref "3E") (pin "8") (pinfunction "O_8") (pintype "output"))
      (node (ref "3F") (pin "5") (pinfunction "I1_5") (pintype "input"))
    )
    (net (code "67") (name "Net-(3FA-I0)") (class "Default")
      (node (ref "3A2") (pin "2") (pinfunction "2_2") (pintype "passive"))
      (node (ref "3F") (pin "1") (pinfunction "I0_1") (pintype "input"))
      (node (ref "5E") (pin "10") (pinfunction "O_10") (pintype "open_collector"))
    )
    (net (code "68") (name "Net-(3FB-I0)") (class "Default")
      (node (ref "3F") (pin "4") (pinfunction "I0_4") (pintype "input"))
      (node (ref "4F") (pin "2") (pinfunction "O_2") (pintype "output"))
    )
    (net (code "69") (name "Net-(3FC-I1)") (class "Default")
      (node (ref "3F") (pin "10") (pinfunction "I1_10") (pintype "input"))
      (node (ref "4E") (pin "13") (pinfunction "O_13") (pintype "output"))
    )
    (net (code "70") (name "Net-(3FC-O)") (class "Default")
      (node (ref "3F") (pin "8") (pinfunction "O_8") (pintype "output"))
      (node (ref "5F") (pin "10") (pinfunction "I1_10") (pintype "input"))
      (node (ref "6F") (pin "4") (pinfunction "D2_4") (pintype "input"))
    )
    (net (code "71") (name "Net-(3FD-I0)") (class "Default")
      (node (ref "3F") (pin "12") (pinfunction "I0_12") (pintype "input"))
      (node (ref "4F") (pin "8") (pinfunction "O_8") (pintype "output"))
      (node (ref "5E") (pin "11") (pinfunction "I_11") (pintype "input"))
    )
    (net (code "72") (name "Net-(3FD-O)") (class "Default")
      (node (ref "3F") (pin "11") (pinfunction "O_11") (pintype "output"))
      (node (ref "4C") (pin "9") (pinfunction "CLK_9") (pintype "input"))
      (node (ref "6F") (pin "9") (pinfunction "CLK_9") (pintype "input"))
    )
    (net (code "73") (name "Net-(4AA-O7)") (class "Default")
      (node (ref "3A1") (pin "2") (pinfunction "2_2") (pintype "passive"))
      (node (ref "4A") (pin "7") (pinfunction "O7_7") (pintype "open_collector"))
      (node (ref "TP1") (pin "TP") (pinfunction "TP_TP") (pintype "input"))
    )
    (net (code "74") (name "Net-(4AA-O8)") (class "Default")
      (node (ref "3A2") (pin "8") (pinfunction "8_8") (pintype "passive"))
      (node (ref "4A") (pin "9") (pinfunction "O8_9") (pintype "open_collector"))
      (node (ref "TP3") (pin "TP") (pinfunction "TP_TP") (pintype "input"))
    )
    (net (code "75") (name "Net-(4AA-~{CE})") (class "Default")
      (node (ref "4A") (pin "15") (pinfunction "~{CE}_15") (pintype "input"))
      (node (ref "5F") (pin "3") (pinfunction "O_3") (pintype "output"))
    )
    (net (code "76") (name "Net-(4BA-A0)") (class "Default")
      (node (ref "4B") (pin "5") (pinfunction "A0_5") (pintype "input"))
      (node (ref "4E") (pin "6") (pinfunction "I1_6") (pintype "input"))
      (node (ref "4F") (pin "4") (pinfunction "O_4") (pintype "output"))
      (node (ref "5F") (pin "1") (pinfunction "I0_1") (pintype "input"))
    )
    (net (code "77") (name "Net-(4BA-~{CE})") (class "Default")
      (node (ref "4B") (pin "13") (pinfunction "~{CE}_13") (pintype "input"))
      (node (ref "4F") (pin "13") (pinfunction "I_13") (pintype "input"))
      (node (ref "5F") (pin "11") (pinfunction "O_11") (pintype "output"))
    )
    (net (code "78") (name "Net-(4DA-D2)") (class "Default")
      (node (ref "4D") (pin "5") (pinfunction "D2_5") (pintype "input"))
      (node (ref "5A") (pin "3") (pinfunction "D1_3") (pintype "input"))
      (node (ref "5C") (pin "2") (pinfunction "Q1_2") (pintype "output"))
    )
    (net (code "79") (name "Net-(4DA-D3)") (class "Default")
      (node (ref "4D") (pin "12") (pinfunction "D3_12") (pintype "input"))
      (node (ref "5A") (pin "6") (pinfunction "D3_6") (pintype "input"))
      (node (ref "5C") (pin "7") (pinfunction "Q2_7") (pintype "output"))
    )
    (net (code "80") (name "Net-(4DA-D4)") (class "Default")
      (node (ref "4D") (pin "13") (pinfunction "D4_13") (pintype "input"))
      (node (ref "5A") (pin "11") (pinfunction "D4_11") (pintype "input"))
      (node (ref "5C") (pin "10") (pinfunction "Q3_10") (pintype "output"))
    )
    (net (code "81") (name "Net-(4DA-Q2)") (class "Default")
      (node (ref "4D") (pin "7") (pinfunction "Q2_7") (pintype "output"))
      (node (ref "5D") (pin "5") (pinfunction "2A_5") (pintype "input"))
      (node (ref "6D") (pin "6") (pinfunction "A3_6") (pintype "input"))
    )
    (net (code "82") (name "Net-(4DA-Q3)") (class "Default")
      (node (ref "4D") (pin "10") (pinfunction "Q3_10") (pintype "output"))
      (node (ref "5D") (pin "11") (pinfunction "3A_11") (pintype "input"))
      (node (ref "6D") (pin "2") (pinfunction "A1_2") (pintype "input"))
    )
    (net (code "83") (name "Net-(4DA-Q4)") (class "Default")
      (node (ref "4D") (pin "15") (pinfunction "Q4_15") (pintype "output"))
      (node (ref "5D") (pin "2") (pinfunction "1A_2") (pintype "input"))
      (node (ref "6D") (pin "14") (pinfunction "A6_14") (pintype "input"))
    )
    (net (code "84") (name "Net-(4EC-O)") (class "Default")
      (node (ref "4E") (pin "10") (pinfunction "O_10") (pintype "output"))
      (node (ref "6E") (pin "14") (pinfunction "A6_14") (pintype "input"))
    )
    (net (code "85") (name "Net-(4FD-I)") (class "Default")
      (node (ref "3A2") (pin "3") (pinfunction "3_3") (pintype "passive"))
      (node (ref "4F") (pin "9") (pinfunction "I_9") (pintype "input"))
      (node (ref "5E") (pin "2") (pinfunction "O_2") (pintype "open_collector"))
    )
    (net (code "86") (name "Net-(4FE-I)") (class "Default")
      (node (ref "4F") (pin "11") (pinfunction "I_11") (pintype "input"))
      (node (ref "5F") (pin "6") (pinfunction "O_6") (pintype "output"))
    )
    (net (code "87") (name "Net-(4FE-O)") (class "Default")
      (node (ref "4F") (pin "10") (pinfunction "O_10") (pintype "output"))
      (node (ref "5E") (pin "3") (pinfunction "I_3") (pintype "input"))
    )
    (net (code "88") (name "Net-(5AA-D2)") (class "Default")
      (node (ref "5A") (pin "4") (pinfunction "D2_4") (pintype "input"))
      (node (ref "5B") (pin "10") (pinfunction "Q3_10") (pintype "output"))
      (node (ref "5D") (pin "3") (pinfunction "1B_3") (pintype "input"))
      (node (ref "6B") (pin "14") (pinfunction "A6_14") (pintype "input"))
    )
    (net (code "89") (name "Net-(5AA-D5)") (class "Default")
      (node (ref "5A") (pin "13") (pinfunction "D5_13") (pintype "input"))
      (node (ref "5B") (pin "7") (pinfunction "Q2_7") (pintype "output"))
      (node (ref "5D") (pin "10") (pinfunction "3B_10") (pintype "input"))
      (node (ref "6B") (pin "2") (pinfunction "A1_2") (pintype "input"))
    )
    (net (code "90") (name "Net-(5AA-D6)") (class "Default")
      (node (ref "5A") (pin "14") (pinfunction "D6_14") (pintype "input"))
      (node (ref "5B") (pin "2") (pinfunction "Q1_2") (pintype "output"))
      (node (ref "5D") (pin "6") (pinfunction "2B_6") (pintype "input"))
      (node (ref "6B") (pin "6") (pinfunction "A3_6") (pintype "input"))
    )
    (net (code "91") (name "Net-(5AA-Q1)") (class "Default")
      (node (ref "5A") (pin "2") (pinfunction "Q1_2") (pintype "output"))
      (node (ref "6A") (pin "6") (pinfunction "A3_6") (pintype "input"))
    )
    (net (code "92") (name "Net-(5AA-Q2)") (class "Default")
      (node (ref "5A") (pin "5") (pinfunction "Q2_5") (pintype "output"))
      (node (ref "6A") (pin "4") (pinfunction "A2_4") (pintype "input"))
    )
    (net (code "93") (name "Net-(5AA-Q3)") (class "Default")
      (node (ref "5A") (pin "7") (pinfunction "Q3_7") (pintype "output"))
      (node (ref "6A") (pin "2") (pinfunction "A1_2") (pintype "input"))
    )
    (net (code "94") (name "Net-(5AA-Q4)") (class "Default")
      (node (ref "5A") (pin "10") (pinfunction "Q4_10") (pintype "output"))
      (node (ref "6A") (pin "14") (pinfunction "A6_14") (pintype "input"))
    )
    (net (code "95") (name "Net-(5AA-Q5)") (class "Default")
      (node (ref "5A") (pin "12") (pinfunction "Q5_12") (pintype "output"))
      (node (ref "6A") (pin "12") (pinfunction "A5_12") (pintype "input"))
    )
    (net (code "96") (name "Net-(5AA-Q6)") (class "Default")
      (node (ref "5A") (pin "15") (pinfunction "Q6_15") (pintype "output"))
      (node (ref "6A") (pin "10") (pinfunction "A4_10") (pintype "input"))
    )
    (net (code "97") (name "Net-(5EB-O)") (class "Default")
      (node (ref "5E") (pin "4") (pinfunction "O_4") (pintype "open_collector"))
      (node (ref "5F") (pin "5") (pinfunction "I1_5") (pintype "input"))
    )
    (net (code "98") (name "Net-(5FC-O)") (class "Default")
      (node (ref "5F") (pin "8") (pinfunction "O_8") (pintype "output"))
      (node (ref "6F") (pin "14") (pinfunction "D6_14") (pintype "input"))
    )
    (net (code "99") (name "VCC") (class "Default")
      (node (ref "3A1") (pin "1") (pinfunction "1_1") (pintype "passive"))
      (node (ref "3A2") (pin "1") (pinfunction "1_1") (pintype "passive"))
      (node (ref "3D") (pin "1") (pinfunction "CLR_1") (pintype "input"))
      (node (ref "3D") (pin "10") (pinfunction "PRE_10") (pintype "input"))
      (node (ref "3D") (pin "12") (pinfunction "D_12") (pintype "input"))
      (node (ref "4C") (pin "1") (pinfunction "CLR_1") (pintype "input"))
      (node (ref "4D") (pin "4") (pinfunction "D1_4") (pintype "input"))
      (node (ref "5A") (pin "1") (pinfunction "CLR_1") (pintype "input"))
      (node (ref "5B") (pin "13") (pinfunction "D4_13") (pintype "input"))
      (node (ref "5C") (pin "13") (pinfunction "D4_13") (pintype "input"))
      (node (ref "5F") (pin "4") (pinfunction "I0_4") (pintype "input"))
      (node (ref "6F") (pin "1") (pinfunction "CLR_1") (pintype "input"))
      (node (ref "6F") (pin "3") (pinfunction "D1_3") (pintype "input"))
      (node (ref "C1") (pin "+") (pinfunction "+_+") (pintype "passive"))
      (node (ref "C10") (pin "1") (pinfunction "1_1") (pintype "passive"))
      (node (ref "C11") (pin "1") (pinfunction "1_1") (pintype "passive"))
      (node (ref "C12") (pin "1") (pinfunction "1_1") (pintype "passive"))
      (node (ref "C13") (pin "1") (pinfunction "1_1") (pintype "passive"))
      (node (ref "C14") (pin "1") (pinfunction "1_1") (pintype "passive"))
      (node (ref "C15") (pin "1") (pinfunction "1_1") (pintype "passive"))
      (node (ref "C16") (pin "1") (pinfunction "1_1") (pintype "passive"))
      (node (ref "C17") (pin "1") (pinfunction "1_1") (pintype "passive"))
      (node (ref "C18") (pin "1") (pinfunction "1_1") (pintype "passive"))
      (node (ref "C19") (pin "1") (pinfunction "1_1") (pintype "passive"))
      (node (ref "C2") (pin "+") (pinfunction "+_+") (pintype "passive"))
      (node (ref "C20") (pin "1") (pinfunction "1_1") (pintype "passive"))
      (node (ref "C21") (pin "1") (pinfunction "1_1") (pintype "passive"))
      (node (ref "C22") (pin "1") (pinfunction "1_1") (pintype "passive"))
      (node (ref "C23") (pin "1") (pinfunction "1_1") (pintype "passive"))
      (node (ref "C24") (pin "1") (pinfunction "1_1") (pintype "passive"))
      (node (ref "C3") (pin "1") (pinfunction "1_1") (pintype "passive"))
      (node (ref "C4") (pin "1") (pinfunction "1_1") (pintype "passive"))
      (node (ref "C5") (pin "1") (pinfunction "1_1") (pintype "passive"))
      (node (ref "C6") (pin "1") (pinfunction "1_1") (pintype "passive"))
      (node (ref "C7") (pin "1") (pinfunction "1_1") (pintype "passive"))
      (node (ref "C8") (pin "1") (pinfunction "1_1") (pintype "passive"))
      (node (ref "C9") (pin "1") (pinfunction "1_1") (pintype "passive"))
      (node (ref "PL1") (pin "1") (pinfunction "S_1") (pintype "passive"))
      (node (ref "PL1") (pin "40") (pinfunction "S_40") (pintype "passive"))
    )
    (net (code "100") (name "unconnected-(3DA-~{Q}-Pad6)") (class "Default")
      (node (ref "3D") (pin "6") (pinfunction "~{Q}_6") (pintype "output"))
    )
    (net (code "101") (name "unconnected-(4DA-Q1-Pad2)") (class "Default")
      (node (ref "4D") (pin "2") (pinfunction "Q1_2") (pintype "output"))
    )
    (net (code "102") (name "unconnected-(4DA-~{Q1}-Pad3)") (class "Default")
      (node (ref "4D") (pin "3") (pinfunction "~{Q1}_3") (pintype "output"))
    )
    (net (code "103") (name "unconnected-(4DA-~{Q2}-Pad6)") (class "Default")
      (node (ref "4D") (pin "6") (pinfunction "~{Q2}_6") (pintype "output"))
    )
    (net (code "104") (name "unconnected-(4DA-~{Q3}-Pad11)") (class "Default")
      (node (ref "4D") (pin "11") (pinfunction "~{Q3}_11") (pintype "output"))
    )
    (net (code "105") (name "unconnected-(4DA-~{Q4}-Pad14)") (class "Default")
      (node (ref "4D") (pin "14") (pinfunction "~{Q4}_14") (pintype "output"))
    )
    (net (code "106") (name "unconnected-(5BA-Q4-Pad15)") (class "Default")
      (node (ref "5B") (pin "15") (pinfunction "Q4_15") (pintype "output"))
    )
    (net (code "107") (name "unconnected-(5BA-~{Q1}-Pad3)") (class "Default")
      (node (ref "5B") (pin "3") (pinfunction "~{Q1}_3") (pintype "output"))
    )
    (net (code "108") (name "unconnected-(5BA-~{Q2}-Pad6)") (class "Default")
      (node (ref "5B") (pin "6") (pinfunction "~{Q2}_6") (pintype "output"))
    )
    (net (code "109") (name "unconnected-(5BA-~{Q3}-Pad11)") (class "Default")
      (node (ref "5B") (pin "11") (pinfunction "~{Q3}_11") (pintype "output"))
    )
    (net (code "110") (name "unconnected-(5BA-~{Q4}-Pad14)") (class "Default")
      (node (ref "5B") (pin "14") (pinfunction "~{Q4}_14") (pintype "output"))
    )
    (net (code "111") (name "unconnected-(5CA-Q4-Pad15)") (class "Default")
      (node (ref "5C") (pin "15") (pinfunction "Q4_15") (pintype "output"))
    )
    (net (code "112") (name "unconnected-(5CA-~{Q1}-Pad3)") (class "Default")
      (node (ref "5C") (pin "3") (pinfunction "~{Q1}_3") (pintype "output"))
    )
    (net (code "113") (name "unconnected-(5CA-~{Q2}-Pad6)") (class "Default")
      (node (ref "5C") (pin "6") (pinfunction "~{Q2}_6") (pintype "output"))
    )
    (net (code "114") (name "unconnected-(5CA-~{Q3}-Pad11)") (class "Default")
      (node (ref "5C") (pin "11") (pinfunction "~{Q3}_11") (pintype "output"))
    )
    (net (code "115") (name "unconnected-(5CA-~{Q4}-Pad14)") (class "Default")
      (node (ref "5C") (pin "14") (pinfunction "~{Q4}_14") (pintype "output"))
    )
    (net (code "116") (name "unconnected-(5DA-4Y-Pad12)") (class "Default")
      (node (ref "5D") (pin "12") (pinfunction "4Y_12") (pintype "tri_state"))
    )
    (net (code "117") (name "unconnected-(6FA-Q1-Pad2)") (class "Default")
      (node (ref "6F") (pin "2") (pinfunction "Q1_2") (pintype "output"))
    )
  )
)
